# GNS530_shematic.net
KiCad netlist of a schematic drawn in EasyEDA
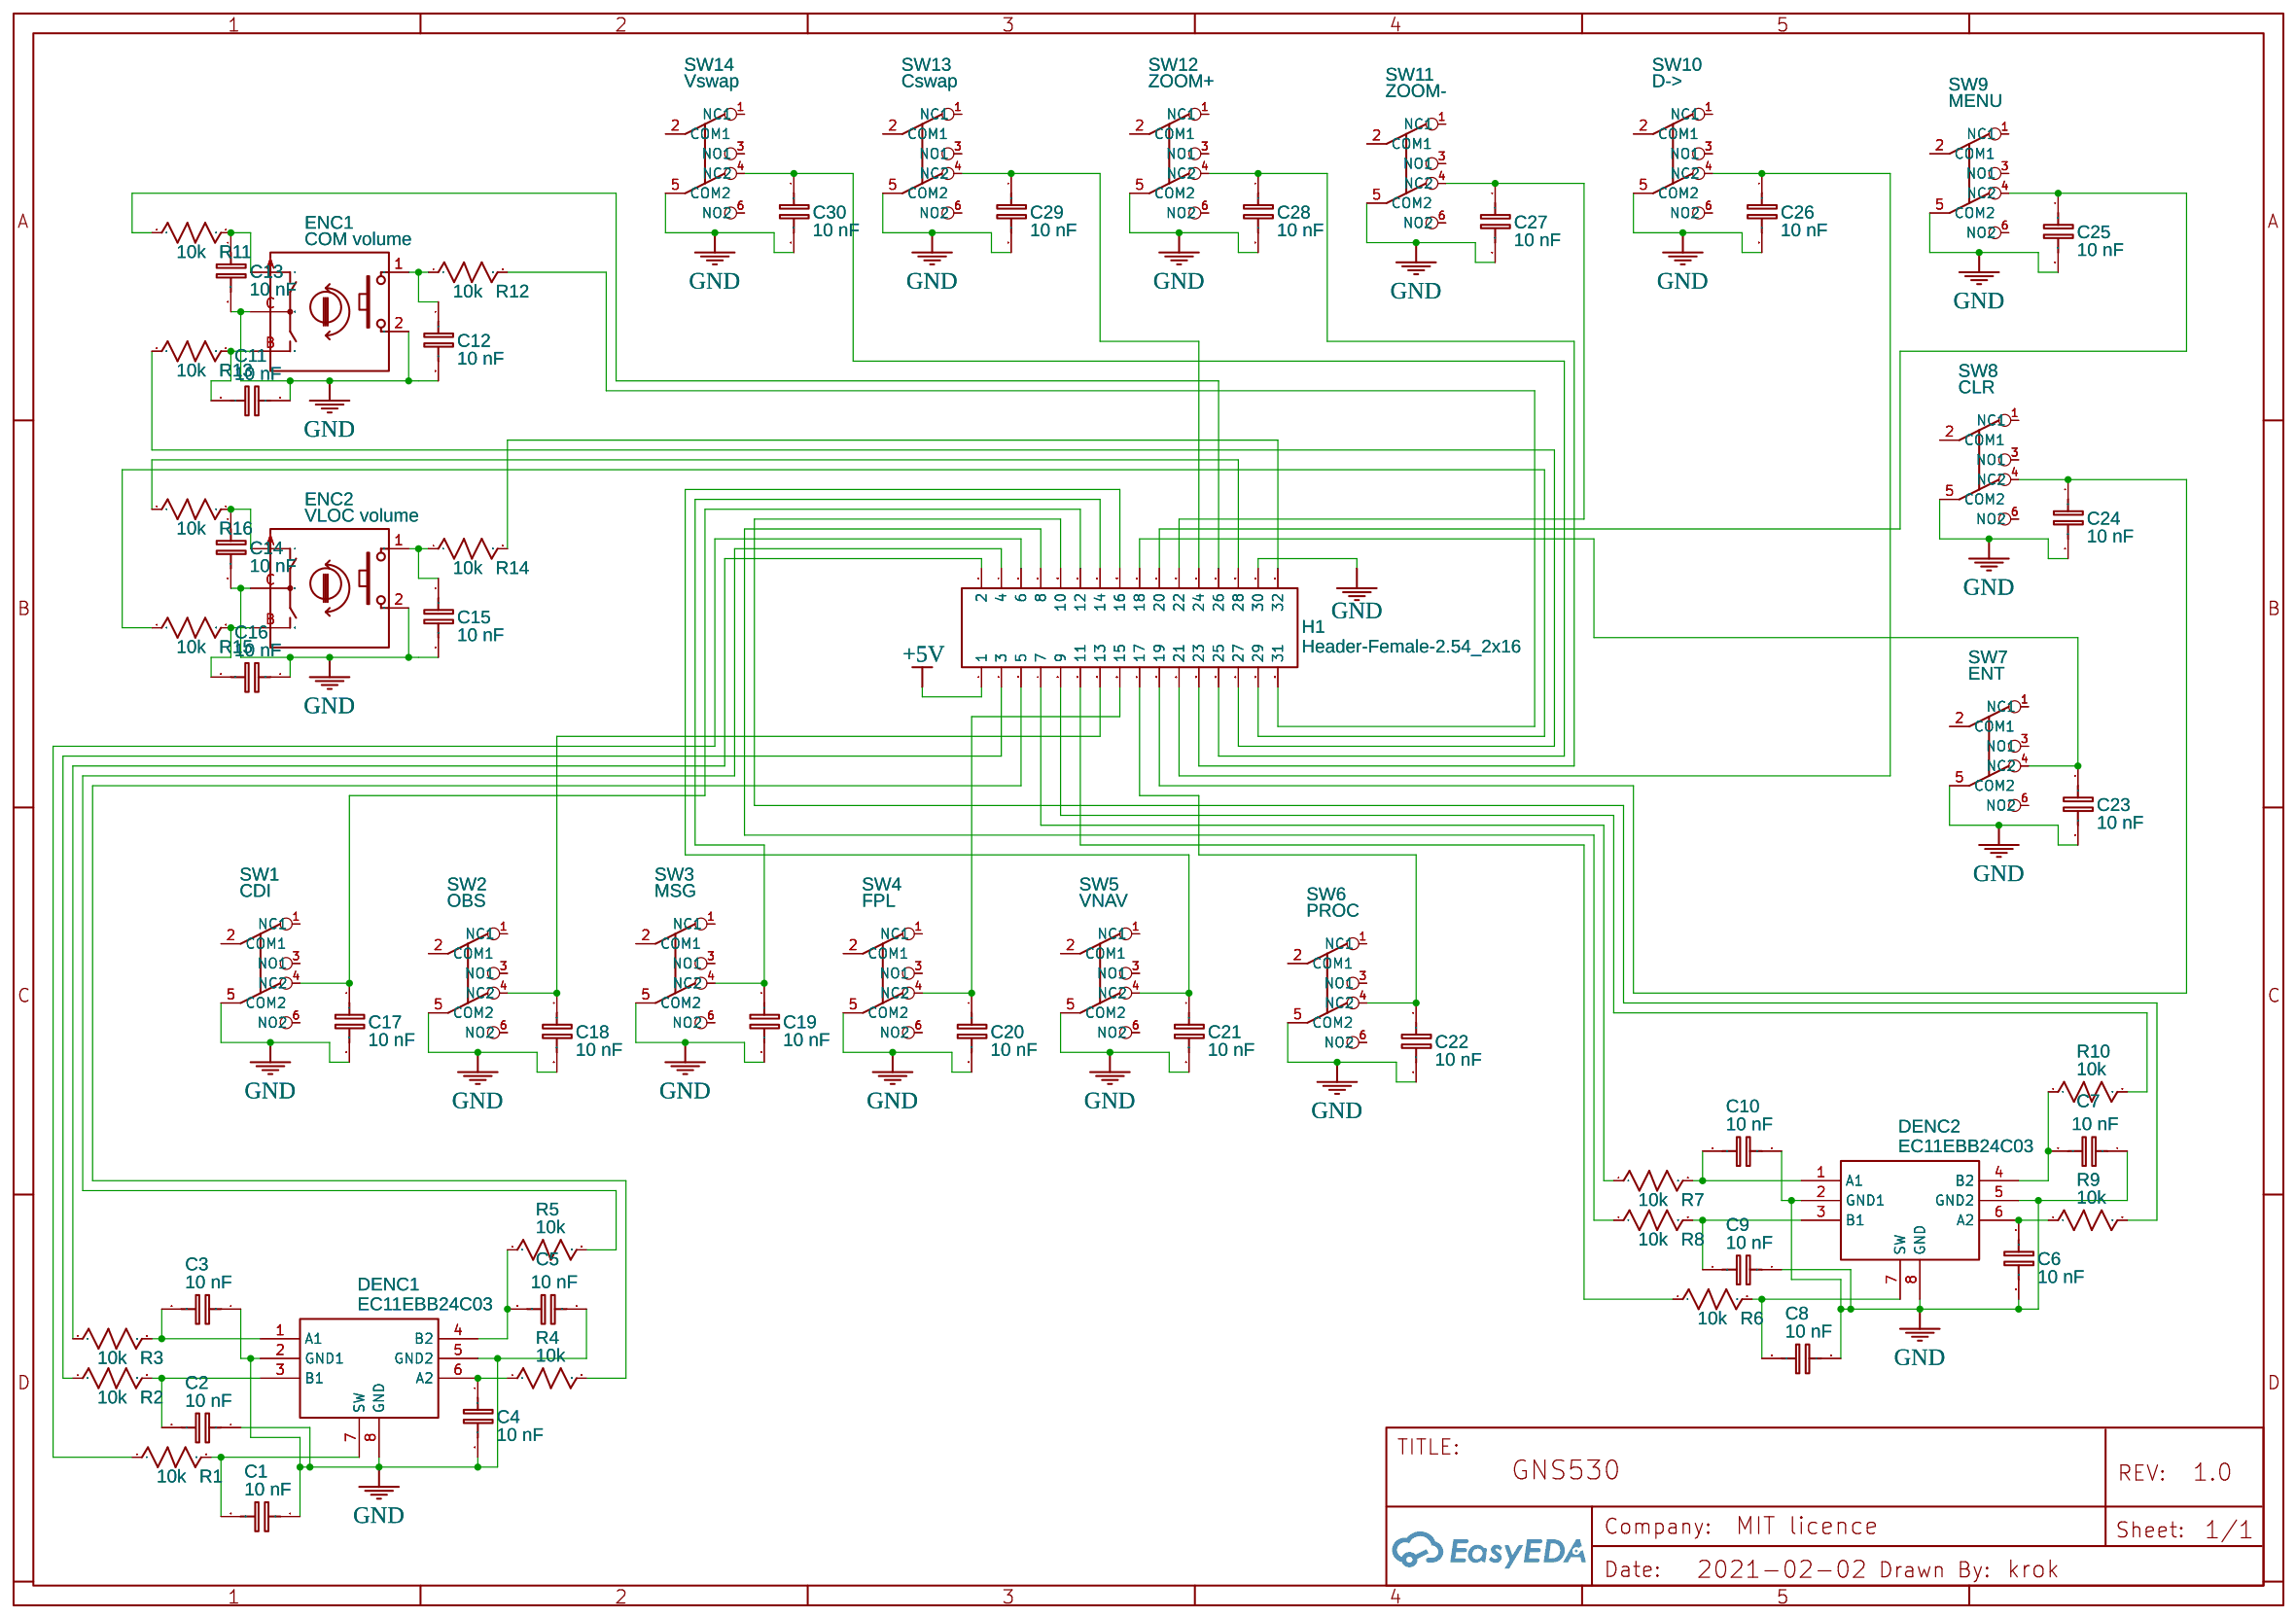
[diagram p0: schematic sheet]

(export (version "E")
  (design (tool "Eeschema 10.0.6"))
  (components
    (comp (ref "C1") (value "10 nF") (libsource (lib "") (part "Capacitor1_EU_3")))
    (comp (ref "C2") (value "10 nF") (libsource (lib "") (part "Capacitor1_EU_3")))
    (comp (ref "C3") (value "10 nF") (libsource (lib "") (part "Capacitor1_EU_4")))
    (comp (ref "C4") (value "10 nF") (libsource (lib "") (part "Capacitor1_EU_2")))
    (comp (ref "C5") (value "10 nF") (libsource (lib "") (part "Capacitor1_EU_6")))
    (comp (ref "C6") (value "10 nF") (libsource (lib "") (part "Capacitor1_EU_5")))
    (comp (ref "C7") (value "10 nF") (libsource (lib "") (part "Capacitor1_EU_4")))
    (comp (ref "C8") (value "10 nF") (libsource (lib "") (part "Capacitor1_EU_4")))
    (comp (ref "C9") (value "10 nF") (libsource (lib "") (part "Capacitor1_EU_4")))
    (comp (ref "C10") (value "10 nF") (libsource (lib "") (part "Capacitor1_EU_4")))
    (comp (ref "C11") (value "10 nF") (libsource (lib "") (part "Capacitor1_EU_3")))
    (comp (ref "C12") (value "10 nF") (libsource (lib "") (part "Capacitor1_EU_2")))
    (comp (ref "C13") (value "10 nF") (libsource (lib "") (part "Capacitor1_EU")))
    (comp (ref "C14") (value "10 nF") (libsource (lib "") (part "Capacitor1_EU")))
    (comp (ref "C15") (value "10 nF") (libsource (lib "") (part "Capacitor1_EU_1")))
    (comp (ref "C16") (value "10 nF") (libsource (lib "") (part "Capacitor1_EU_4")))
    (comp (ref "C17") (value "10 nF") (libsource (lib "") (part "Capacitor1_EU_1")))
    (comp (ref "C18") (value "10 nF") (libsource (lib "") (part "Capacitor1_EU_1")))
    (comp (ref "C19") (value "10 nF") (libsource (lib "") (part "Capacitor1_EU_1")))
    (comp (ref "C20") (value "10 nF") (libsource (lib "") (part "Capacitor1_EU_1")))
    (comp (ref "C21") (value "10 nF") (libsource (lib "") (part "Capacitor1_EU_5")))
    (comp (ref "C22") (value "10 nF") (libsource (lib "") (part "Capacitor1_EU_5")))
    (comp (ref "C23") (value "10 nF") (libsource (lib "") (part "Capacitor1_EU_5")))
    (comp (ref "C24") (value "10 nF") (libsource (lib "") (part "Capacitor1_EU")))
    (comp (ref "C25") (value "10 nF") (libsource (lib "") (part "Capacitor1_EU")))
    (comp (ref "C26") (value "10 nF") (libsource (lib "") (part "Capacitor1_EU")))
    (comp (ref "C27") (value "10 nF") (libsource (lib "") (part "Capacitor1_EU")))
    (comp (ref "C28") (value "10 nF") (libsource (lib "") (part "Capacitor1_EU")))
    (comp (ref "C29") (value "10 nF") (libsource (lib "") (part "Capacitor1_EU_2")))
    (comp (ref "C30") (value "10 nF") (libsource (lib "") (part "Capacitor1_EU_2")))
    (comp (ref "DENC1") (value "EC11EBB24C03") (libsource (lib "") (part "EC11EBB24C03")))
    (comp (ref "DENC2") (value "EC11EBB24C03") (libsource (lib "") (part "EC11EBB24C03")))
    (comp (ref "ENC1")
      (value "COM volume")
      (fields (field (name "BOM_Manufacturer Part") "Encoder EC11"))
      (libsource (lib "") (part "Encoder EC11"))
    )
    (comp (ref "ENC2")
      (value "VLOC volume")
      (fields (field (name "BOM_Manufacturer Part") "Encoder EC11"))
      (libsource (lib "") (part "Encoder EC11"))
    )
    (comp (ref "H1")
      (value "Header-Female-2.54_2x16")
      (fields
        (field (name "BOM_Manufacturer Part") "2.54mm,2×16Double female header")
        (field (name "BOM_Supplier Part") "C24778")
      )
      (libsource (lib "") (part "Header-Female-2.54_2x16"))
    )
    (comp (ref "R1") (value "10k") (libsource (lib "") (part "R_0201_US")))
    (comp (ref "R2") (value "10k") (libsource (lib "") (part "R_0201_US")))
    (comp (ref "R3") (value "10k") (libsource (lib "") (part "R_0201_US")))
    (comp (ref "R4") (value "10k") (libsource (lib "") (part "R_0201_US")))
    (comp (ref "R5") (value "10k") (libsource (lib "") (part "R_0201_US")))
    (comp (ref "R6") (value "10k") (libsource (lib "") (part "R_0201_US")))
    (comp (ref "R7") (value "10k") (libsource (lib "") (part "R_0201_US")))
    (comp (ref "R8") (value "10k") (libsource (lib "") (part "R_0201_US")))
    (comp (ref "R9") (value "10k") (libsource (lib "") (part "R_0201_US")))
    (comp (ref "R10") (value "10k") (libsource (lib "") (part "R_0201_US")))
    (comp (ref "R11") (value "10k") (libsource (lib "") (part "R_0201_US")))
    (comp (ref "R12") (value "10k") (libsource (lib "") (part "R_0201_US")))
    (comp (ref "R13") (value "10k") (libsource (lib "") (part "R_0201_US")))
    (comp (ref "R14") (value "10k") (libsource (lib "") (part "R_0201_US")))
    (comp (ref "R15") (value "10k") (libsource (lib "") (part "R_0201_US")))
    (comp (ref "R16") (value "10k") (libsource (lib "") (part "R_0201_US")))
    (comp (ref "SW1") (value "CDI") (libsource (lib "") (part "SW_PUSH_DPDT")))
    (comp (ref "SW2") (value "OBS") (libsource (lib "") (part "SW_PUSH_DPDT")))
    (comp (ref "SW3") (value "MSG") (libsource (lib "") (part "SW_PUSH_DPDT")))
    (comp (ref "SW4") (value "FPL") (libsource (lib "") (part "SW_PUSH_DPDT")))
    (comp (ref "SW5") (value "VNAV") (libsource (lib "") (part "SW_PUSH_DPDT")))
    (comp (ref "SW6") (value "PROC") (libsource (lib "") (part "SW_PUSH_DPDT")))
    (comp (ref "SW7") (value "ENT") (libsource (lib "") (part "SW_PUSH_DPDT")))
    (comp (ref "SW8") (value "CLR") (libsource (lib "") (part "SW_PUSH_DPDT")))
    (comp (ref "SW9") (value "MENU") (libsource (lib "") (part "SW_PUSH_DPDT")))
    (comp (ref "SW10") (value "D->") (libsource (lib "") (part "SW_PUSH_DPDT")))
    (comp (ref "SW11") (value "ZOOM-") (libsource (lib "") (part "SW_PUSH_DPDT")))
    (comp (ref "SW12") (value "ZOOM+") (libsource (lib "") (part "SW_PUSH_DPDT")))
    (comp (ref "SW13") (value "Cswap") (libsource (lib "") (part "SW_PUSH_DPDT")))
    (comp (ref "SW14") (value "Vswap") (libsource (lib "") (part "SW_PUSH_DPDT")))
  )
  (nets
    (net (code "1") (name "+5V") (class "Default")
      (node (ref "H1") (pin "1") (pinfunction "1_1") (pintype "input"))
    )
    (net (code "2") (name "GND") (class "Default")
      (node (ref "C1") (pin "1") (pinfunction "1_1") (pintype "unspecified"))
      (node (ref "C10") (pin "1") (pinfunction "1_1") (pintype "unspecified"))
      (node (ref "C11") (pin "1") (pinfunction "1_1") (pintype "unspecified"))
      (node (ref "C12") (pin "2") (pinfunction "2_2") (pintype "unspecified"))
      (node (ref "C13") (pin "2") (pinfunction "2_2") (pintype "unspecified"))
      (node (ref "C14") (pin "2") (pinfunction "2_2") (pintype "unspecified"))
      (node (ref "C15") (pin "2") (pinfunction "2_2") (pintype "unspecified"))
      (node (ref "C16") (pin "1") (pinfunction "1_1") (pintype "unspecified"))
      (node (ref "C17") (pin "2") (pinfunction "2_2") (pintype "unspecified"))
      (node (ref "C18") (pin "2") (pinfunction "2_2") (pintype "unspecified"))
      (node (ref "C19") (pin "2") (pinfunction "2_2") (pintype "unspecified"))
      (node (ref "C2") (pin "1") (pinfunction "1_1") (pintype "unspecified"))
      (node (ref "C20") (pin "2") (pinfunction "2_2") (pintype "unspecified"))
      (node (ref "C21") (pin "2") (pinfunction "2_2") (pintype "unspecified"))
      (node (ref "C22") (pin "2") (pinfunction "2_2") (pintype "unspecified"))
      (node (ref "C23") (pin "2") (pinfunction "2_2") (pintype "unspecified"))
      (node (ref "C24") (pin "2") (pinfunction "2_2") (pintype "unspecified"))
      (node (ref "C25") (pin "2") (pinfunction "2_2") (pintype "unspecified"))
      (node (ref "C26") (pin "2") (pinfunction "2_2") (pintype "unspecified"))
      (node (ref "C27") (pin "2") (pinfunction "2_2") (pintype "unspecified"))
      (node (ref "C28") (pin "2") (pinfunction "2_2") (pintype "unspecified"))
      (node (ref "C29") (pin "2") (pinfunction "2_2") (pintype "unspecified"))
      (node (ref "C3") (pin "1") (pinfunction "1_1") (pintype "unspecified"))
      (node (ref "C30") (pin "2") (pinfunction "2_2") (pintype "unspecified"))
      (node (ref "C4") (pin "2") (pinfunction "2_2") (pintype "unspecified"))
      (node (ref "C5") (pin "1") (pinfunction "1_1") (pintype "unspecified"))
      (node (ref "C6") (pin "2") (pinfunction "2_2") (pintype "unspecified"))
      (node (ref "C7") (pin "1") (pinfunction "1_1") (pintype "unspecified"))
      (node (ref "C8") (pin "1") (pinfunction "1_1") (pintype "unspecified"))
      (node (ref "C9") (pin "1") (pinfunction "1_1") (pintype "unspecified"))
      (node (ref "DENC1") (pin "2") (pinfunction "GND1_2") (pintype "unspecified"))
      (node (ref "DENC1") (pin "5") (pinfunction "GND2_5") (pintype "unspecified"))
      (node (ref "DENC1") (pin "8") (pinfunction "GND_8") (pintype "unspecified"))
      (node (ref "DENC2") (pin "2") (pinfunction "GND1_2") (pintype "unspecified"))
      (node (ref "DENC2") (pin "5") (pinfunction "GND2_5") (pintype "unspecified"))
      (node (ref "DENC2") (pin "8") (pinfunction "GND_8") (pintype "unspecified"))
      (node (ref "ENC1") (pin "2") (pinfunction "2_2") (pintype "unspecified"))
      (node (ref "ENC1") (pin "C") (pinfunction "C_C") (pintype "unspecified"))
      (node (ref "ENC2") (pin "2") (pinfunction "2_2") (pintype "unspecified"))
      (node (ref "ENC2") (pin "C") (pinfunction "C_C") (pintype "unspecified"))
      (node (ref "H1") (pin "30") (pinfunction "30_30") (pintype "input"))
      (node (ref "SW1") (pin "5") (pinfunction "COM2_5") (pintype "unspecified"))
      (node (ref "SW10") (pin "5") (pinfunction "COM2_5") (pintype "unspecified"))
      (node (ref "SW11") (pin "5") (pinfunction "COM2_5") (pintype "unspecified"))
      (node (ref "SW12") (pin "5") (pinfunction "COM2_5") (pintype "unspecified"))
      (node (ref "SW13") (pin "5") (pinfunction "COM2_5") (pintype "unspecified"))
      (node (ref "SW14") (pin "5") (pinfunction "COM2_5") (pintype "unspecified"))
      (node (ref "SW2") (pin "5") (pinfunction "COM2_5") (pintype "unspecified"))
      (node (ref "SW3") (pin "5") (pinfunction "COM2_5") (pintype "unspecified"))
      (node (ref "SW4") (pin "5") (pinfunction "COM2_5") (pintype "unspecified"))
      (node (ref "SW5") (pin "5") (pinfunction "COM2_5") (pintype "unspecified"))
      (node (ref "SW6") (pin "5") (pinfunction "COM2_5") (pintype "unspecified"))
      (node (ref "SW7") (pin "5") (pinfunction "COM2_5") (pintype "unspecified"))
      (node (ref "SW8") (pin "5") (pinfunction "COM2_5") (pintype "unspecified"))
      (node (ref "SW9") (pin "5") (pinfunction "COM2_5") (pintype "unspecified"))
    )
    (net (code "3") (name "Net-(C11-Pad2)") (class "Default")
      (node (ref "C11") (pin "2") (pinfunction "2_2") (pintype "unspecified"))
      (node (ref "ENC1") (pin "B") (pinfunction "B_B") (pintype "unspecified"))
      (node (ref "R13") (pin "2") (pinfunction "2_2") (pintype "unspecified"))
    )
    (net (code "4") (name "Net-(C12-Pad1)") (class "Default")
      (node (ref "C12") (pin "1") (pinfunction "1_1") (pintype "unspecified"))
      (node (ref "ENC1") (pin "1") (pinfunction "1_1") (pintype "unspecified"))
      (node (ref "R12") (pin "1") (pinfunction "1_1") (pintype "unspecified"))
    )
    (net (code "5") (name "Net-(C13-Pad1)") (class "Default")
      (node (ref "C13") (pin "1") (pinfunction "1_1") (pintype "unspecified"))
      (node (ref "ENC1") (pin "A") (pinfunction "A_A") (pintype "unspecified"))
      (node (ref "R11") (pin "2") (pinfunction "2_2") (pintype "unspecified"))
    )
    (net (code "6") (name "Net-(C14-Pad1)") (class "Default")
      (node (ref "C14") (pin "1") (pinfunction "1_1") (pintype "unspecified"))
      (node (ref "ENC2") (pin "A") (pinfunction "A_A") (pintype "unspecified"))
      (node (ref "R16") (pin "2") (pinfunction "2_2") (pintype "unspecified"))
    )
    (net (code "7") (name "Net-(C15-Pad1)") (class "Default")
      (node (ref "C15") (pin "1") (pinfunction "1_1") (pintype "unspecified"))
      (node (ref "ENC2") (pin "1") (pinfunction "1_1") (pintype "unspecified"))
      (node (ref "R14") (pin "1") (pinfunction "1_1") (pintype "unspecified"))
    )
    (net (code "8") (name "Net-(C16-Pad2)") (class "Default")
      (node (ref "C16") (pin "2") (pinfunction "2_2") (pintype "unspecified"))
      (node (ref "ENC2") (pin "B") (pinfunction "B_B") (pintype "unspecified"))
      (node (ref "R15") (pin "2") (pinfunction "2_2") (pintype "unspecified"))
    )
    (net (code "9") (name "Net-(DENC1-A1)") (class "Default")
      (node (ref "C3") (pin "2") (pinfunction "2_2") (pintype "unspecified"))
      (node (ref "DENC1") (pin "1") (pinfunction "A1_1") (pintype "unspecified"))
      (node (ref "R3") (pin "2") (pinfunction "2_2") (pintype "unspecified"))
    )
    (net (code "10") (name "Net-(DENC1-A2)") (class "Default")
      (node (ref "C4") (pin "1") (pinfunction "1_1") (pintype "unspecified"))
      (node (ref "DENC1") (pin "6") (pinfunction "A2_6") (pintype "unspecified"))
      (node (ref "R4") (pin "1") (pinfunction "1_1") (pintype "unspecified"))
    )
    (net (code "11") (name "Net-(DENC1-B1)") (class "Default")
      (node (ref "C2") (pin "2") (pinfunction "2_2") (pintype "unspecified"))
      (node (ref "DENC1") (pin "3") (pinfunction "B1_3") (pintype "unspecified"))
      (node (ref "R2") (pin "2") (pinfunction "2_2") (pintype "unspecified"))
    )
    (net (code "12") (name "Net-(DENC1-B2)") (class "Default")
      (node (ref "C5") (pin "2") (pinfunction "2_2") (pintype "unspecified"))
      (node (ref "DENC1") (pin "4") (pinfunction "B2_4") (pintype "unspecified"))
      (node (ref "R5") (pin "1") (pinfunction "1_1") (pintype "unspecified"))
    )
    (net (code "13") (name "Net-(DENC1-SW)") (class "Default")
      (node (ref "C1") (pin "2") (pinfunction "2_2") (pintype "unspecified"))
      (node (ref "DENC1") (pin "7") (pinfunction "SW_7") (pintype "unspecified"))
      (node (ref "R1") (pin "2") (pinfunction "2_2") (pintype "unspecified"))
    )
    (net (code "14") (name "Net-(DENC2-A1)") (class "Default")
      (node (ref "C10") (pin "2") (pinfunction "2_2") (pintype "unspecified"))
      (node (ref "DENC2") (pin "1") (pinfunction "A1_1") (pintype "unspecified"))
      (node (ref "R7") (pin "2") (pinfunction "2_2") (pintype "unspecified"))
    )
    (net (code "15") (name "Net-(DENC2-A2)") (class "Default")
      (node (ref "C6") (pin "1") (pinfunction "1_1") (pintype "unspecified"))
      (node (ref "DENC2") (pin "6") (pinfunction "A2_6") (pintype "unspecified"))
      (node (ref "R9") (pin "1") (pinfunction "1_1") (pintype "unspecified"))
    )
    (net (code "16") (name "Net-(DENC2-B1)") (class "Default")
      (node (ref "C9") (pin "2") (pinfunction "2_2") (pintype "unspecified"))
      (node (ref "DENC2") (pin "3") (pinfunction "B1_3") (pintype "unspecified"))
      (node (ref "R8") (pin "2") (pinfunction "2_2") (pintype "unspecified"))
    )
    (net (code "17") (name "Net-(DENC2-B2)") (class "Default")
      (node (ref "C7") (pin "2") (pinfunction "2_2") (pintype "unspecified"))
      (node (ref "DENC2") (pin "4") (pinfunction "B2_4") (pintype "unspecified"))
      (node (ref "R10") (pin "1") (pinfunction "1_1") (pintype "unspecified"))
    )
    (net (code "18") (name "Net-(DENC2-SW)") (class "Default")
      (node (ref "C8") (pin "2") (pinfunction "2_2") (pintype "unspecified"))
      (node (ref "DENC2") (pin "7") (pinfunction "SW_7") (pintype "unspecified"))
      (node (ref "R6") (pin "2") (pinfunction "2_2") (pintype "unspecified"))
    )
    (net (code "19") (name "Net-(H1-Pad2)") (class "Default")
      (node (ref "H1") (pin "2") (pinfunction "2_2") (pintype "input"))
      (node (ref "R3") (pin "1") (pinfunction "1_1") (pintype "unspecified"))
    )
    (net (code "20") (name "Net-(H1-Pad3)") (class "Default")
      (node (ref "H1") (pin "3") (pinfunction "3_3") (pintype "input"))
      (node (ref "R2") (pin "1") (pinfunction "1_1") (pintype "unspecified"))
    )
    (net (code "21") (name "Net-(H1-Pad4)") (class "Default")
      (node (ref "H1") (pin "4") (pinfunction "4_4") (pintype "input"))
      (node (ref "R5") (pin "2") (pinfunction "2_2") (pintype "unspecified"))
    )
    (net (code "22") (name "Net-(H1-Pad5)") (class "Default")
      (node (ref "H1") (pin "5") (pinfunction "5_5") (pintype "input"))
      (node (ref "R4") (pin "2") (pinfunction "2_2") (pintype "unspecified"))
    )
    (net (code "23") (name "Net-(H1-Pad6)") (class "Default")
      (node (ref "H1") (pin "6") (pinfunction "6_6") (pintype "input"))
      (node (ref "R1") (pin "1") (pinfunction "1_1") (pintype "unspecified"))
    )
    (net (code "24") (name "Net-(H1-Pad7)") (class "Default")
      (node (ref "H1") (pin "7") (pinfunction "7_7") (pintype "input"))
      (node (ref "R7") (pin "1") (pinfunction "1_1") (pintype "unspecified"))
    )
    (net (code "25") (name "Net-(H1-Pad8)") (class "Default")
      (node (ref "H1") (pin "8") (pinfunction "8_8") (pintype "input"))
      (node (ref "R8") (pin "1") (pinfunction "1_1") (pintype "unspecified"))
    )
    (net (code "26") (name "Net-(H1-Pad9)") (class "Default")
      (node (ref "H1") (pin "9") (pinfunction "9_9") (pintype "input"))
      (node (ref "R10") (pin "2") (pinfunction "2_2") (pintype "unspecified"))
    )
    (net (code "27") (name "Net-(H1-Pad10)") (class "Default")
      (node (ref "H1") (pin "10") (pinfunction "10_10") (pintype "input"))
      (node (ref "R9") (pin "2") (pinfunction "2_2") (pintype "unspecified"))
    )
    (net (code "28") (name "Net-(H1-Pad11)") (class "Default")
      (node (ref "H1") (pin "11") (pinfunction "11_11") (pintype "input"))
      (node (ref "R6") (pin "1") (pinfunction "1_1") (pintype "unspecified"))
    )
    (net (code "29") (name "Net-(H1-Pad26)") (class "Default")
      (node (ref "H1") (pin "26") (pinfunction "26_26") (pintype "input"))
      (node (ref "R11") (pin "1") (pinfunction "1_1") (pintype "unspecified"))
    )
    (net (code "30") (name "Net-(H1-Pad27)") (class "Default")
      (node (ref "H1") (pin "27") (pinfunction "27_27") (pintype "input"))
      (node (ref "R13") (pin "1") (pinfunction "1_1") (pintype "unspecified"))
    )
    (net (code "31") (name "Net-(H1-Pad28)") (class "Default")
      (node (ref "H1") (pin "28") (pinfunction "28_28") (pintype "input"))
      (node (ref "R16") (pin "1") (pinfunction "1_1") (pintype "unspecified"))
    )
    (net (code "32") (name "Net-(H1-Pad29)") (class "Default")
      (node (ref "H1") (pin "29") (pinfunction "29_29") (pintype "input"))
      (node (ref "R15") (pin "1") (pinfunction "1_1") (pintype "unspecified"))
    )
    (net (code "33") (name "Net-(H1-Pad31)") (class "Default")
      (node (ref "H1") (pin "31") (pinfunction "31_31") (pintype "input"))
      (node (ref "R12") (pin "2") (pinfunction "2_2") (pintype "unspecified"))
    )
    (net (code "34") (name "Net-(H1-Pad32)") (class "Default")
      (node (ref "H1") (pin "32") (pinfunction "32_32") (pintype "input"))
      (node (ref "R14") (pin "2") (pinfunction "2_2") (pintype "unspecified"))
    )
    (net (code "35") (name "Net-(SW1-NC2)") (class "Default")
      (node (ref "C17") (pin "1") (pinfunction "1_1") (pintype "unspecified"))
      (node (ref "H1") (pin "12") (pinfunction "12_12") (pintype "input"))
      (node (ref "SW1") (pin "4") (pinfunction "NC2_4") (pintype "unspecified"))
    )
    (net (code "36") (name "Net-(SW2-NC2)") (class "Default")
      (node (ref "C18") (pin "1") (pinfunction "1_1") (pintype "unspecified"))
      (node (ref "H1") (pin "13") (pinfunction "13_13") (pintype "input"))
      (node (ref "SW2") (pin "4") (pinfunction "NC2_4") (pintype "unspecified"))
    )
    (net (code "37") (name "Net-(SW3-NC2)") (class "Default")
      (node (ref "C19") (pin "1") (pinfunction "1_1") (pintype "unspecified"))
      (node (ref "H1") (pin "14") (pinfunction "14_14") (pintype "input"))
      (node (ref "SW3") (pin "4") (pinfunction "NC2_4") (pintype "unspecified"))
    )
    (net (code "38") (name "Net-(SW4-NC2)") (class "Default")
      (node (ref "C20") (pin "1") (pinfunction "1_1") (pintype "unspecified"))
      (node (ref "H1") (pin "15") (pinfunction "15_15") (pintype "input"))
      (node (ref "SW4") (pin "4") (pinfunction "NC2_4") (pintype "unspecified"))
    )
    (net (code "39") (name "Net-(SW5-NC2)") (class "Default")
      (node (ref "C21") (pin "1") (pinfunction "1_1") (pintype "unspecified"))
      (node (ref "H1") (pin "16") (pinfunction "16_16") (pintype "input"))
      (node (ref "SW5") (pin "4") (pinfunction "NC2_4") (pintype "unspecified"))
    )
    (net (code "40") (name "Net-(SW6-NC2)") (class "Default")
      (node (ref "C22") (pin "1") (pinfunction "1_1") (pintype "unspecified"))
      (node (ref "H1") (pin "17") (pinfunction "17_17") (pintype "input"))
      (node (ref "SW6") (pin "4") (pinfunction "NC2_4") (pintype "unspecified"))
    )
    (net (code "41") (name "Net-(SW7-NC2)") (class "Default")
      (node (ref "C23") (pin "1") (pinfunction "1_1") (pintype "unspecified"))
      (node (ref "H1") (pin "18") (pinfunction "18_18") (pintype "input"))
      (node (ref "SW7") (pin "4") (pinfunction "NC2_4") (pintype "unspecified"))
    )
    (net (code "42") (name "Net-(SW8-NC2)") (class "Default")
      (node (ref "C24") (pin "1") (pinfunction "1_1") (pintype "unspecified"))
      (node (ref "H1") (pin "19") (pinfunction "19_19") (pintype "input"))
      (node (ref "SW8") (pin "4") (pinfunction "NC2_4") (pintype "unspecified"))
    )
    (net (code "43") (name "Net-(SW9-NC2)") (class "Default")
      (node (ref "C25") (pin "1") (pinfunction "1_1") (pintype "unspecified"))
      (node (ref "H1") (pin "20") (pinfunction "20_20") (pintype "input"))
      (node (ref "SW9") (pin "4") (pinfunction "NC2_4") (pintype "unspecified"))
    )
    (net (code "44") (name "Net-(SW10-NC2)") (class "Default")
      (node (ref "C26") (pin "1") (pinfunction "1_1") (pintype "unspecified"))
      (node (ref "H1") (pin "21") (pinfunction "21_21") (pintype "input"))
      (node (ref "SW10") (pin "4") (pinfunction "NC2_4") (pintype "unspecified"))
    )
    (net (code "45") (name "Net-(SW11-NC2)") (class "Default")
      (node (ref "C27") (pin "1") (pinfunction "1_1") (pintype "unspecified"))
      (node (ref "H1") (pin "22") (pinfunction "22_22") (pintype "input"))
      (node (ref "SW11") (pin "4") (pinfunction "NC2_4") (pintype "unspecified"))
    )
    (net (code "46") (name "Net-(SW12-NC2)") (class "Default")
      (node (ref "C28") (pin "1") (pinfunction "1_1") (pintype "unspecified"))
      (node (ref "H1") (pin "23") (pinfunction "23_23") (pintype "input"))
      (node (ref "SW12") (pin "4") (pinfunction "NC2_4") (pintype "unspecified"))
    )
    (net (code "47") (name "Net-(SW13-NC2)") (class "Default")
      (node (ref "C29") (pin "1") (pinfunction "1_1") (pintype "unspecified"))
      (node (ref "H1") (pin "24") (pinfunction "24_24") (pintype "input"))
      (node (ref "SW13") (pin "4") (pinfunction "NC2_4") (pintype "unspecified"))
    )
    (net (code "48") (name "Net-(SW14-NC2)") (class "Default")
      (node (ref "C30") (pin "1") (pinfunction "1_1") (pintype "unspecified"))
      (node (ref "H1") (pin "25") (pinfunction "25_25") (pintype "input"))
      (node (ref "SW14") (pin "4") (pinfunction "NC2_4") (pintype "unspecified"))
    )
    (net (code "49") (name "unconnected-(SW1-COM1-Pad2)") (class "Default")
      (node (ref "SW1") (pin "2") (pinfunction "COM1_2") (pintype "unspecified"))
    )
    (net (code "50") (name "unconnected-(SW1-NC1-Pad1)") (class "Default")
      (node (ref "SW1") (pin "1") (pinfunction "NC1_1") (pintype "unspecified"))
    )
    (net (code "51") (name "unconnected-(SW1-NO1-Pad3)") (class "Default")
      (node (ref "SW1") (pin "3") (pinfunction "NO1_3") (pintype "unspecified"))
    )
    (net (code "52") (name "unconnected-(SW1-NO2-Pad6)") (class "Default")
      (node (ref "SW1") (pin "6") (pinfunction "NO2_6") (pintype "unspecified"))
    )
    (net (code "53") (name "unconnected-(SW2-COM1-Pad2)") (class "Default")
      (node (ref "SW2") (pin "2") (pinfunction "COM1_2") (pintype "unspecified"))
    )
    (net (code "54") (name "unconnected-(SW2-NC1-Pad1)") (class "Default")
      (node (ref "SW2") (pin "1") (pinfunction "NC1_1") (pintype "unspecified"))
    )
    (net (code "55") (name "unconnected-(SW2-NO1-Pad3)") (class "Default")
      (node (ref "SW2") (pin "3") (pinfunction "NO1_3") (pintype "unspecified"))
    )
    (net (code "56") (name "unconnected-(SW2-NO2-Pad6)") (class "Default")
      (node (ref "SW2") (pin "6") (pinfunction "NO2_6") (pintype "unspecified"))
    )
    (net (code "57") (name "unconnected-(SW3-COM1-Pad2)") (class "Default")
      (node (ref "SW3") (pin "2") (pinfunction "COM1_2") (pintype "unspecified"))
    )
    (net (code "58") (name "unconnected-(SW3-NC1-Pad1)") (class "Default")
      (node (ref "SW3") (pin "1") (pinfunction "NC1_1") (pintype "unspecified"))
    )
    (net (code "59") (name "unconnected-(SW3-NO1-Pad3)") (class "Default")
      (node (ref "SW3") (pin "3") (pinfunction "NO1_3") (pintype "unspecified"))
    )
    (net (code "60") (name "unconnected-(SW3-NO2-Pad6)") (class "Default")
      (node (ref "SW3") (pin "6") (pinfunction "NO2_6") (pintype "unspecified"))
    )
    (net (code "61") (name "unconnected-(SW4-COM1-Pad2)") (class "Default")
      (node (ref "SW4") (pin "2") (pinfunction "COM1_2") (pintype "unspecified"))
    )
    (net (code "62") (name "unconnected-(SW4-NC1-Pad1)") (class "Default")
      (node (ref "SW4") (pin "1") (pinfunction "NC1_1") (pintype "unspecified"))
    )
    (net (code "63") (name "unconnected-(SW4-NO1-Pad3)") (class "Default")
      (node (ref "SW4") (pin "3") (pinfunction "NO1_3") (pintype "unspecified"))
    )
    (net (code "64") (name "unconnected-(SW4-NO2-Pad6)") (class "Default")
      (node (ref "SW4") (pin "6") (pinfunction "NO2_6") (pintype "unspecified"))
    )
    (net (code "65") (name "unconnected-(SW5-COM1-Pad2)") (class "Default")
      (node (ref "SW5") (pin "2") (pinfunction "COM1_2") (pintype "unspecified"))
    )
    (net (code "66") (name "unconnected-(SW5-NC1-Pad1)") (class "Default")
      (node (ref "SW5") (pin "1") (pinfunction "NC1_1") (pintype "unspecified"))
    )
    (net (code "67") (name "unconnected-(SW5-NO1-Pad3)") (class "Default")
      (node (ref "SW5") (pin "3") (pinfunction "NO1_3") (pintype "unspecified"))
    )
    (net (code "68") (name "unconnected-(SW5-NO2-Pad6)") (class "Default")
      (node (ref "SW5") (pin "6") (pinfunction "NO2_6") (pintype "unspecified"))
    )
    (net (code "69") (name "unconnected-(SW6-COM1-Pad2)") (class "Default")
      (node (ref "SW6") (pin "2") (pinfunction "COM1_2") (pintype "unspecified"))
    )
    (net (code "70") (name "unconnected-(SW6-NC1-Pad1)") (class "Default")
      (node (ref "SW6") (pin "1") (pinfunction "NC1_1") (pintype "unspecified"))
    )
    (net (code "71") (name "unconnected-(SW6-NO1-Pad3)") (class "Default")
      (node (ref "SW6") (pin "3") (pinfunction "NO1_3") (pintype "unspecified"))
    )
    (net (code "72") (name "unconnected-(SW6-NO2-Pad6)") (class "Default")
      (node (ref "SW6") (pin "6") (pinfunction "NO2_6") (pintype "unspecified"))
    )
    (net (code "73") (name "unconnected-(SW7-COM1-Pad2)") (class "Default")
      (node (ref "SW7") (pin "2") (pinfunction "COM1_2") (pintype "unspecified"))
    )
    (net (code "74") (name "unconnected-(SW7-NC1-Pad1)") (class "Default")
      (node (ref "SW7") (pin "1") (pinfunction "NC1_1") (pintype "unspecified"))
    )
    (net (code "75") (name "unconnected-(SW7-NO1-Pad3)") (class "Default")
      (node (ref "SW7") (pin "3") (pinfunction "NO1_3") (pintype "unspecified"))
    )
    (net (code "76") (name "unconnected-(SW7-NO2-Pad6)") (class "Default")
      (node (ref "SW7") (pin "6") (pinfunction "NO2_6") (pintype "unspecified"))
    )
    (net (code "77") (name "unconnected-(SW8-COM1-Pad2)") (class "Default")
      (node (ref "SW8") (pin "2") (pinfunction "COM1_2") (pintype "unspecified"))
    )
    (net (code "78") (name "unconnected-(SW8-NC1-Pad1)") (class "Default")
      (node (ref "SW8") (pin "1") (pinfunction "NC1_1") (pintype "unspecified"))
    )
    (net (code "79") (name "unconnected-(SW8-NO1-Pad3)") (class "Default")
      (node (ref "SW8") (pin "3") (pinfunction "NO1_3") (pintype "unspecified"))
    )
    (net (code "80") (name "unconnected-(SW8-NO2-Pad6)") (class "Default")
      (node (ref "SW8") (pin "6") (pinfunction "NO2_6") (pintype "unspecified"))
    )
    (net (code "81") (name "unconnected-(SW9-COM1-Pad2)") (class "Default")
      (node (ref "SW9") (pin "2") (pinfunction "COM1_2") (pintype "unspecified"))
    )
    (net (code "82") (name "unconnected-(SW9-NC1-Pad1)") (class "Default")
      (node (ref "SW9") (pin "1") (pinfunction "NC1_1") (pintype "unspecified"))
    )
    (net (code "83") (name "unconnected-(SW9-NO1-Pad3)") (class "Default")
      (node (ref "SW9") (pin "3") (pinfunction "NO1_3") (pintype "unspecified"))
    )
    (net (code "84") (name "unconnected-(SW9-NO2-Pad6)") (class "Default")
      (node (ref "SW9") (pin "6") (pinfunction "NO2_6") (pintype "unspecified"))
    )
    (net (code "85") (name "unconnected-(SW10-COM1-Pad2)") (class "Default")
      (node (ref "SW10") (pin "2") (pinfunction "COM1_2") (pintype "unspecified"))
    )
    (net (code "86") (name "unconnected-(SW10-NC1-Pad1)") (class "Default")
      (node (ref "SW10") (pin "1") (pinfunction "NC1_1") (pintype "unspecified"))
    )
    (net (code "87") (name "unconnected-(SW10-NO1-Pad3)") (class "Default")
      (node (ref "SW10") (pin "3") (pinfunction "NO1_3") (pintype "unspecified"))
    )
    (net (code "88") (name "unconnected-(SW10-NO2-Pad6)") (class "Default")
      (node (ref "SW10") (pin "6") (pinfunction "NO2_6") (pintype "unspecified"))
    )
    (net (code "89") (name "unconnected-(SW11-COM1-Pad2)") (class "Default")
      (node (ref "SW11") (pin "2") (pinfunction "COM1_2") (pintype "unspecified"))
    )
    (net (code "90") (name "unconnected-(SW11-NC1-Pad1)") (class "Default")
      (node (ref "SW11") (pin "1") (pinfunction "NC1_1") (pintype "unspecified"))
    )
    (net (code "91") (name "unconnected-(SW11-NO1-Pad3)") (class "Default")
      (node (ref "SW11") (pin "3") (pinfunction "NO1_3") (pintype "unspecified"))
    )
    (net (code "92") (name "unconnected-(SW11-NO2-Pad6)") (class "Default")
      (node (ref "SW11") (pin "6") (pinfunction "NO2_6") (pintype "unspecified"))
    )
    (net (code "93") (name "unconnected-(SW12-COM1-Pad2)") (class "Default")
      (node (ref "SW12") (pin "2") (pinfunction "COM1_2") (pintype "unspecified"))
    )
    (net (code "94") (name "unconnected-(SW12-NC1-Pad1)") (class "Default")
      (node (ref "SW12") (pin "1") (pinfunction "NC1_1") (pintype "unspecified"))
    )
    (net (code "95") (name "unconnected-(SW12-NO1-Pad3)") (class "Default")
      (node (ref "SW12") (pin "3") (pinfunction "NO1_3") (pintype "unspecified"))
    )
    (net (code "96") (name "unconnected-(SW12-NO2-Pad6)") (class "Default")
      (node (ref "SW12") (pin "6") (pinfunction "NO2_6") (pintype "unspecified"))
    )
    (net (code "97") (name "unconnected-(SW13-COM1-Pad2)") (class "Default")
      (node (ref "SW13") (pin "2") (pinfunction "COM1_2") (pintype "unspecified"))
    )
    (net (code "98") (name "unconnected-(SW13-NC1-Pad1)") (class "Default")
      (node (ref "SW13") (pin "1") (pinfunction "NC1_1") (pintype "unspecified"))
    )
    (net (code "99") (name "unconnected-(SW13-NO1-Pad3)") (class "Default")
      (node (ref "SW13") (pin "3") (pinfunction "NO1_3") (pintype "unspecified"))
    )
    (net (code "100") (name "unconnected-(SW13-NO2-Pad6)") (class "Default")
      (node (ref "SW13") (pin "6") (pinfunction "NO2_6") (pintype "unspecified"))
    )
    (net (code "101") (name "unconnected-(SW14-COM1-Pad2)") (class "Default")
      (node (ref "SW14") (pin "2") (pinfunction "COM1_2") (pintype "unspecified"))
    )
    (net (code "102") (name "unconnected-(SW14-NC1-Pad1)") (class "Default")
      (node (ref "SW14") (pin "1") (pinfunction "NC1_1") (pintype "unspecified"))
    )
    (net (code "103") (name "unconnected-(SW14-NO1-Pad3)") (class "Default")
      (node (ref "SW14") (pin "3") (pinfunction "NO1_3") (pintype "unspecified"))
    )
    (net (code "104") (name "unconnected-(SW14-NO2-Pad6)") (class "Default")
      (node (ref "SW14") (pin "6") (pinfunction "NO2_6") (pintype "unspecified"))
    )
  )
)
